# PowerFilters.net
KiCad netlist of a schematic drawn in Altium Designer
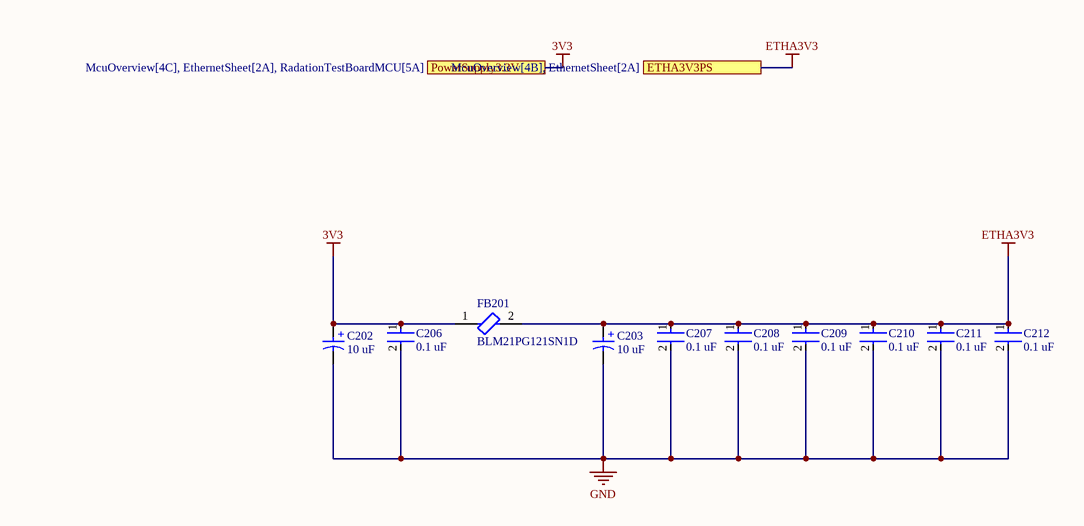
[diagram p0: PowerFilters.SchDoc]

(export (version "E")
  (design (tool "Eeschema 10.0.6"))
  (components
    (comp (ref "C202")
      (value "10 uF")
      (footprint "WCAP-HTG5_D6.3H8")
      (description "870575873001 Cap, 10Uf, 63V, Alu Elec, Hybrid, Rad Rohs Compliant: Yes 870575873001")
      (libsource (lib "Altium Content Vault") (part "Capacitor_Polarized"))
    )
    (comp (ref "C203")
      (value "10 uF")
      (footprint "WCAP-HTG5_D6.3H8")
      (description "870575873001 Cap, 10Uf, 63V, Alu Elec, Hybrid, Rad Rohs Compliant: Yes 870575873001")
      (libsource (lib "Altium Content Vault") (part "Capacitor_Polarized"))
    )
    (comp (ref "C206")
      (value "0.1 uF")
      (footprint "FP-CC0603-DA-IPC_A")
      (description "CAP CER 0.1UF 50V X7R 0603 CC0603JRX7R9BB104")
      (fields (field (name "TOLERANCE") "5%"))
      (libsource (lib "Altium Content Vault") (part "02cd4be3c70576c341d710602a673aa"))
    )
    (comp (ref "C207")
      (value "0.1 uF")
      (footprint "FP-CC0603-DA-IPC_A")
      (description "CAP CER 0.1UF 50V X7R 0603 CC0603JRX7R9BB104")
      (fields (field (name "TOLERANCE") "5%"))
      (libsource (lib "Altium Content Vault") (part "02cd4be3c70576c341d710602a673aa"))
    )
    (comp (ref "C208")
      (value "0.1 uF")
      (footprint "FP-CC0603-DA-IPC_A")
      (description "CAP CER 0.1UF 50V X7R 0603 CC0603JRX7R9BB104")
      (fields (field (name "TOLERANCE") "5%"))
      (libsource (lib "Altium Content Vault") (part "02cd4be3c70576c341d710602a673aa"))
    )
    (comp (ref "C209")
      (value "0.1 uF")
      (footprint "FP-CC0603-DA-IPC_A")
      (description "CAP CER 0.1UF 50V X7R 0603 CC0603JRX7R9BB104")
      (fields (field (name "TOLERANCE") "5%"))
      (libsource (lib "Altium Content Vault") (part "02cd4be3c70576c341d710602a673aa"))
    )
    (comp (ref "C210")
      (value "0.1 uF")
      (footprint "FP-CC0603-DA-IPC_A")
      (description "CAP CER 0.1UF 50V X7R 0603 CC0603JRX7R9BB104")
      (fields (field (name "TOLERANCE") "5%"))
      (libsource (lib "Altium Content Vault") (part "02cd4be3c70576c341d710602a673aa"))
    )
    (comp (ref "C211")
      (value "0.1 uF")
      (footprint "FP-CC0603-DA-IPC_A")
      (description "CAP CER 0.1UF 50V X7R 0603 CC0603JRX7R9BB104")
      (fields (field (name "TOLERANCE") "5%"))
      (libsource (lib "Altium Content Vault") (part "02cd4be3c70576c341d710602a673aa"))
    )
    (comp (ref "C212")
      (value "0.1 uF")
      (footprint "FP-CC0603-DA-IPC_A")
      (description "CAP CER 0.1UF 50V X7R 0603 CC0603JRX7R9BB104")
      (fields (field (name "TOLERANCE") "5%"))
      (libsource (lib "Altium Content Vault") (part "02cd4be3c70576c341d710602a673aa"))
    )
    (comp (ref "FB201")
      (value "BLM21PG121SN1D")
      (footprint "FP-BLM21-0_2-t0_85-e0_5-d-IPC_C")
      (description "Chip Ferrite Bead, 0805, 120Ω @ 100MHz, 0.03Ω, 25%, 3A")
      (fields (field (name "TOLERANCE") "25%"))
      (libsource (lib "Altium Content Vault") (part "5f30dd21d616792df468990f7003faa"))
    )
  )
  (nets
    (net (code "1") (name "3V3") (class "Default")
      (node (ref "C202") (pin "1") (pinfunction "P_1") (pintype "passive"))
      (node (ref "C206") (pin "1") (pinfunction "1_1") (pintype "passive"))
      (node (ref "FB201") (pin "1") (pinfunction "1_1") (pintype "passive"))
    )
    (net (code "2") (name "ETHA3V3") (class "Default")
      (node (ref "C203") (pin "1") (pinfunction "P_1") (pintype "passive"))
      (node (ref "C207") (pin "1") (pinfunction "1_1") (pintype "passive"))
      (node (ref "C208") (pin "1") (pinfunction "1_1") (pintype "passive"))
      (node (ref "C209") (pin "1") (pinfunction "1_1") (pintype "passive"))
      (node (ref "C210") (pin "1") (pinfunction "1_1") (pintype "passive"))
      (node (ref "C211") (pin "1") (pinfunction "1_1") (pintype "passive"))
      (node (ref "C212") (pin "1") (pinfunction "1_1") (pintype "passive"))
      (node (ref "FB201") (pin "2") (pinfunction "2_2") (pintype "passive"))
    )
    (net (code "3") (name "GND") (class "Default")
      (node (ref "C202") (pin "2") (pinfunction "N_2") (pintype "passive"))
      (node (ref "C203") (pin "2") (pinfunction "N_2") (pintype "passive"))
      (node (ref "C206") (pin "2") (pinfunction "2_2") (pintype "passive"))
      (node (ref "C207") (pin "2") (pinfunction "2_2") (pintype "passive"))
      (node (ref "C208") (pin "2") (pinfunction "2_2") (pintype "passive"))
      (node (ref "C209") (pin "2") (pinfunction "2_2") (pintype "passive"))
      (node (ref "C210") (pin "2") (pinfunction "2_2") (pintype "passive"))
      (node (ref "C211") (pin "2") (pinfunction "2_2") (pintype "passive"))
      (node (ref "C212") (pin "2") (pinfunction "2_2") (pintype "passive"))
    )
  )
)
